# leds_mem_sensor.net
KiCad netlist of a schematic drawn in Altium Designer
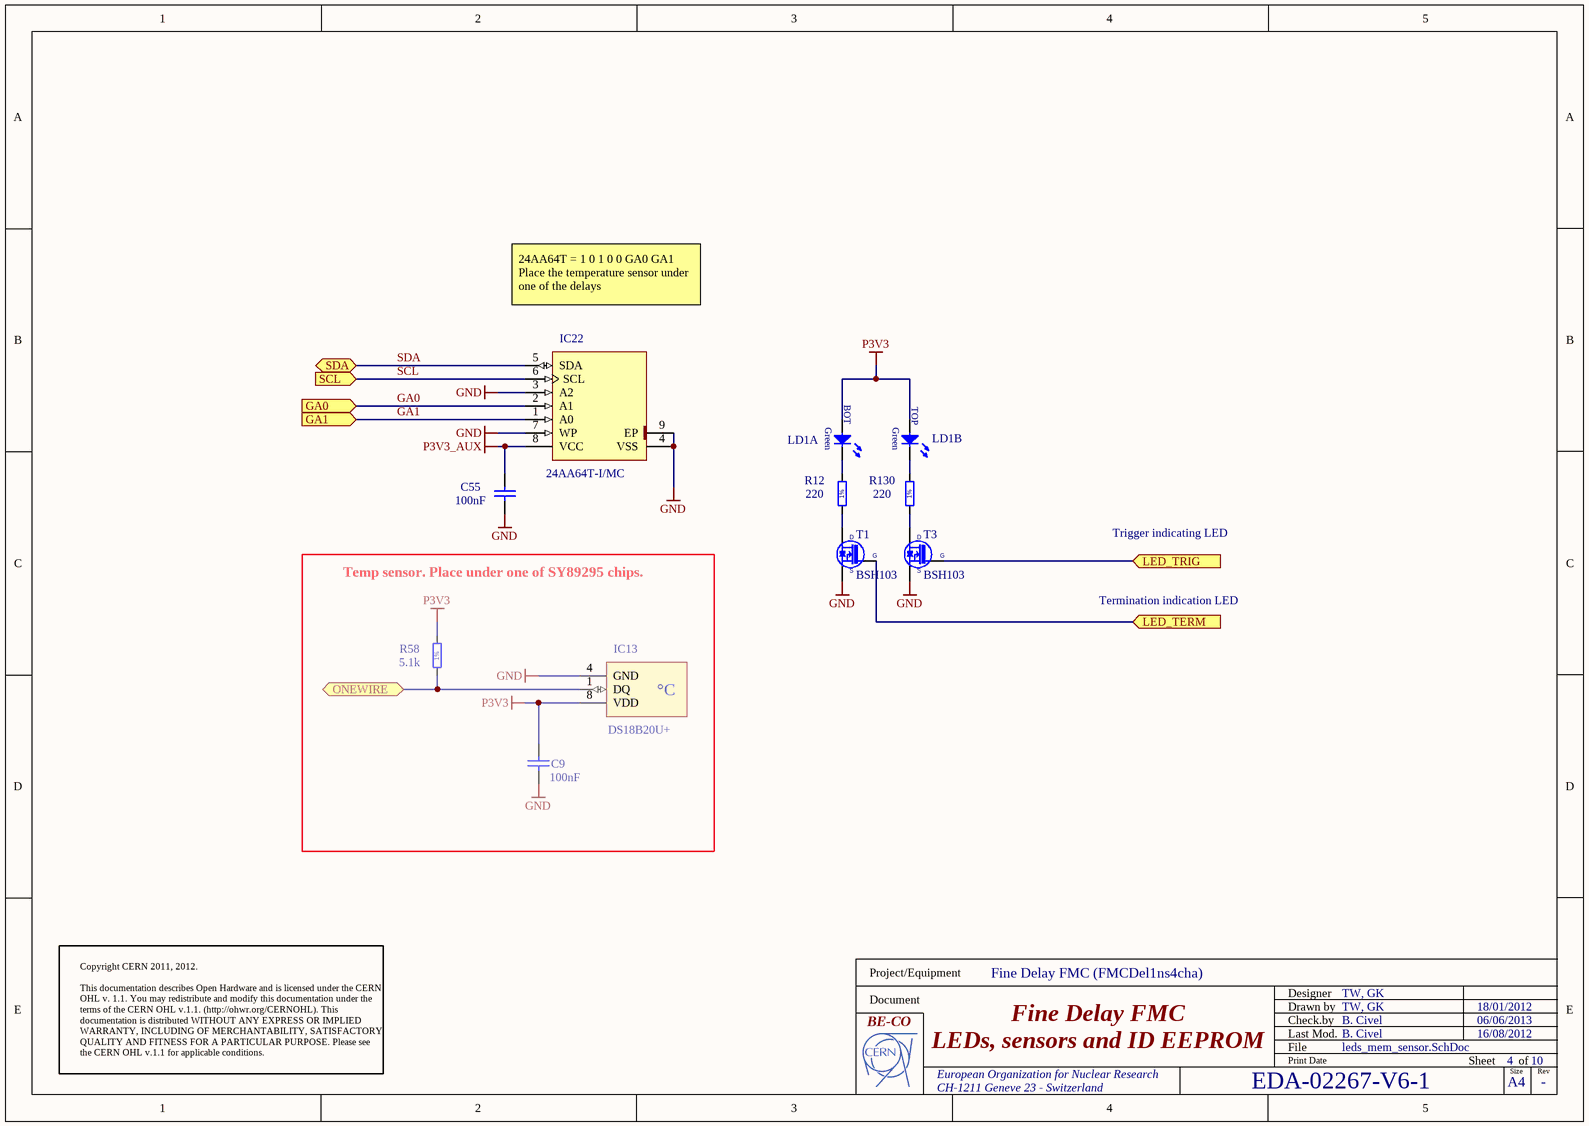
[diagram p0: leds_mem_sensor.SchDoc]

(export (version "E")
  (design (tool "Eeschema 10.0.6"))
  (components
    (comp (ref "C9")
      (value "100nF")
      (footprint "CAPC1608X87N")
      (description "Non-polarised capacitor")
      (fields
        (field (name "PART NUMBER") "CC0603_100NF_50V_10%_X7R")
        (field (name "VOLTAGE") "50V")
        (field (name "AUTHOR") "CERN DEM JLC")
      )
      (libsource (lib "Capacitors") (part "Capacitor - non polarized"))
    )
    (comp (ref "C55")
      (value "100nF")
      (footprint "CAPC1608X87N")
      (description "Non-polarised capacitor")
      (fields
        (field (name "PART NUMBER") "CC0603_100NF_50V_10%_X7R")
        (field (name "VOLTAGE") "50V")
        (field (name "AUTHOR") "CERN DEM JLC")
      )
      (libsource (lib "Capacitors") (part "Capacitor - non polarized"))
    )
    (comp (ref "IC13")
      (value "DS18B20U+")
      (footprint "SOP65P490X110-8N")
      (description "Programmable Resolution 1-Wire Digital Thermometer")
      (fields (field (name "MANUFACTURER") "DALLAS MAXIM") (field (name "AUTHOR") "CERN DEM JLC"))
      (libsource (lib "ICs And Semiconductors") (part "DS18B20U+"))
    )
    (comp (ref "IC22")
      (value "24AA64T-I/MC")
      (footprint "SON50P300X200X100-9N-S175X155")
      (description "1.7-5.5V 64K I2C Serial EEPROM")
      (fields (field (name "MANUFACTURER") "MICROCHIP TECHNOLOGY") (field (name "AUTHOR") "CERN DEM JLC"))
      (libsource (lib "ICs And Semiconductors") (part "24AA64T-I/MC"))
    )
    (comp (ref "LD1")
      (value "Green/Green")
      (footprint "LED_DIALIGHT_571-0122-100F")
      (description "LED x2 Green 1C2A-BOT_3C4A-TOP")
      (fields
        (field (name "PART NUMBER") "LED_DIALIGHT_571-0122-100F")
        (field (name "MANUFACTURER") "DIALIGHT")
        (field (name "AUTHOR") "CERN DEM JLC")
      )
      (libsource (lib "ICs And Semiconductors") (part "LED x2 Green 1C2A-BOT_3C4A-TOP"))
    )
    (comp (ref "R12")
      (value "220")
      (footprint "RESC1608X55N")
      (description "Resistor - 1%")
      (fields
        (field (name "PART NUMBER") "R0603_220R_1%_0.1W_100PPM")
        (field (name "POWER") "0.1W")
        (field (name "AUTHOR") "CERN DEM JLC")
      )
      (libsource (lib "Resistors") (part "Resistor - 1%"))
    )
    (comp (ref "R58")
      (value "5.1k")
      (footprint "RESC1608X55N")
      (description "Resistor - 1%")
      (fields
        (field (name "PART NUMBER") "R0603_5K1_1%_0.1W_100PPM")
        (field (name "POWER") "0.1W")
        (field (name "AUTHOR") "CERN DEM JLC")
      )
      (libsource (lib "Resistors") (part "Resistor - 1%"))
    )
    (comp (ref "R130")
      (value "220")
      (footprint "RESC1608X55N")
      (description "Resistor - 1%")
      (fields
        (field (name "PART NUMBER") "R0603_220R_1%_0.1W_100PPM")
        (field (name "POWER") "0.1W")
        (field (name "AUTHOR") "CERN DEM JLC")
      )
      (libsource (lib "Resistors") (part "Resistor - 1%"))
    )
    (comp (ref "T1")
      (value "BSH103")
      (footprint "SOT95P230X110-3N")
      (description "N-CHANNEL MOSFET WITH DIODE")
      (fields (field (name "MANUFACTURER") "NXP SEMICONDUCTORS") (field (name "AUTHOR") "CERN DEM JLC"))
      (libsource (lib "ICs And Semiconductors") (part "N-MOSFET-D 1G 2S 3D"))
    )
    (comp (ref "T3")
      (value "BSH103")
      (footprint "SOT95P230X110-3N")
      (description "N-CHANNEL MOSFET WITH DIODE")
      (fields (field (name "MANUFACTURER") "NXP SEMICONDUCTORS") (field (name "AUTHOR") "CERN DEM JLC"))
      (libsource (lib "ICs And Semiconductors") (part "N-MOSFET-D 1G 2S 3D"))
    )
  )
  (nets
    (net (code "1") (name "/GA0") (class "Default")
      (node (ref "IC22") (pin "2") (pinfunction "A1_2") (pintype "input"))
    )
    (net (code "2") (name "/GA1") (class "Default")
      (node (ref "IC22") (pin "1") (pinfunction "A0_1") (pintype "input"))
    )
    (net (code "3") (name "/LED_TERM") (class "Default")
      (node (ref "T1") (pin "1") (pinfunction "G_1") (pintype "passive"))
    )
    (net (code "4") (name "/LED_TRIG") (class "Default")
      (node (ref "T3") (pin "1") (pinfunction "G_1") (pintype "passive"))
    )
    (net (code "5") (name "/ONEWIRE") (class "Default")
      (node (ref "IC13") (pin "1") (pinfunction "DQ_1") (pintype "bidirectional"))
      (node (ref "R58") (pin "1") (pinfunction "1_1") (pintype "passive"))
    )
    (net (code "6") (name "/SCL") (class "Default")
      (node (ref "IC22") (pin "6") (pinfunction "SCL_6") (pintype "input"))
    )
    (net (code "7") (name "/SDA") (class "Default")
      (node (ref "IC22") (pin "5") (pinfunction "SDA_5") (pintype "bidirectional"))
    )
    (net (code "8") (name "GND") (class "Default")
      (node (ref "C55") (pin "2") (pinfunction "2_2") (pintype "passive"))
      (node (ref "C9") (pin "2") (pinfunction "2_2") (pintype "passive"))
      (node (ref "IC13") (pin "4") (pinfunction "GND_4") (pintype "power_in"))
      (node (ref "IC22") (pin "3") (pinfunction "A2_3") (pintype "input"))
      (node (ref "IC22") (pin "4") (pinfunction "VSS_4") (pintype "power_in"))
      (node (ref "IC22") (pin "7") (pinfunction "WP_7") (pintype "input"))
      (node (ref "IC22") (pin "9") (pinfunction "EP_9") (pintype "power_in"))
      (node (ref "T1") (pin "2") (pinfunction "S_2") (pintype "passive"))
      (node (ref "T3") (pin "2") (pinfunction "S_2") (pintype "passive"))
    )
    (net (code "9") (name "Net-(LD1A-C)") (class "Default")
      (node (ref "LD1") (pin "1") (pinfunction "C_1") (pintype "passive"))
      (node (ref "R12") (pin "2") (pinfunction "2_2") (pintype "passive"))
    )
    (net (code "10") (name "Net-(LD1B-C)") (class "Default")
      (node (ref "LD1") (pin "3") (pinfunction "C_3") (pintype "passive"))
      (node (ref "R130") (pin "2") (pinfunction "2_2") (pintype "passive"))
    )
    (net (code "11") (name "Net-(T1-D)") (class "Default")
      (node (ref "R12") (pin "1") (pinfunction "1_1") (pintype "passive"))
      (node (ref "T1") (pin "3") (pinfunction "D_3") (pintype "passive"))
    )
    (net (code "12") (name "Net-(T3-D)") (class "Default")
      (node (ref "R130") (pin "1") (pinfunction "1_1") (pintype "passive"))
      (node (ref "T3") (pin "3") (pinfunction "D_3") (pintype "passive"))
    )
    (net (code "13") (name "P3V3") (class "Default")
      (node (ref "C9") (pin "1") (pinfunction "1_1") (pintype "passive"))
      (node (ref "IC13") (pin "8") (pinfunction "VDD_8") (pintype "power_in"))
      (node (ref "LD1") (pin "2") (pinfunction "A_2") (pintype "passive"))
      (node (ref "LD1") (pin "4") (pinfunction "A_4") (pintype "passive"))
      (node (ref "R58") (pin "2") (pinfunction "2_2") (pintype "passive"))
    )
    (net (code "14") (name "P3V3_AUX") (class "Default")
      (node (ref "C55") (pin "1") (pinfunction "1_1") (pintype "passive"))
      (node (ref "IC22") (pin "8") (pinfunction "VCC_8") (pintype "power_in"))
    )
  )
)
